# PM.net
KiCad netlist of a schematic drawn in Altium Designer
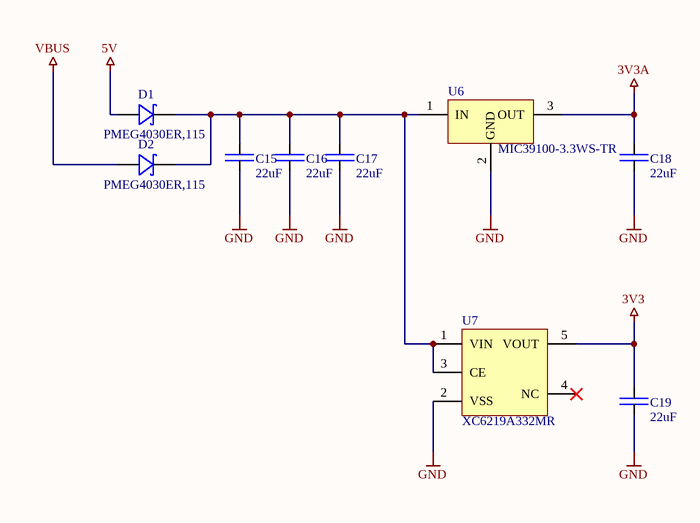
[diagram p0: PM.SchDoc]

(export (version "E")
  (design (tool "Eeschema 10.0.6"))
  (components
    (comp (ref "C15")
      (value "22uF")
      (footprint "SMD Keramikkondensator 0805")
      (description "SMD Ceramic Capacitor E6")
      (libsource (lib "Ceramic Capacitors-E6") (part "E6 - 22uF"))
    )
    (comp (ref "C16")
      (value "22uF")
      (footprint "SMD Keramikkondensator 0805")
      (description "SMD Ceramic Capacitor E6")
      (libsource (lib "Ceramic Capacitors-E6") (part "E6 - 22uF"))
    )
    (comp (ref "C17")
      (value "22uF")
      (footprint "SMD Keramikkondensator 0805")
      (description "SMD Ceramic Capacitor E6")
      (libsource (lib "Ceramic Capacitors-E6") (part "E6 - 22uF"))
    )
    (comp (ref "C18")
      (value "22uF")
      (footprint "SMD Keramikkondensator 0805")
      (description "SMD Ceramic Capacitor E6")
      (libsource (lib "Ceramic Capacitors-E6") (part "E6 - 22uF"))
    )
    (comp (ref "C19")
      (value "22uF")
      (footprint "SMD Keramikkondensator 0805")
      (description "SMD Ceramic Capacitor E6")
      (libsource (lib "Ceramic Capacitors-E6") (part "E6 - 22uF"))
    )
    (comp (ref "D1")
      (value "PMEG4030ER,115")
      (footprint "SMD Diode SOD-123")
      (description "Diode Schottky 3A Surface Mount CFP3")
      (libsource (lib "Diodes") (part "PMEG4030ER,115"))
    )
    (comp (ref "D2")
      (value "PMEG4030ER,115")
      (footprint "SMD Diode SOD-123")
      (description "Diode Schottky 3A Surface Mount CFP3")
      (libsource (lib "Diodes") (part "PMEG4030ER,115"))
    )
    (comp (ref "U6")
      (value "MIC39100-3.3WS-TR")
      (footprint "SMD IC SOT-223-3")
      (description "Linear Voltage Regulator IC Positive Fixed 1 Output 1A SOT-223-3")
      (libsource (lib "Voltage-Converter") (part "MIC39100-3.3WS-TR"))
    )
    (comp (ref "U7")
      (value "XC6219A332MR")
      (footprint "SMD IC SOT-23-5")
      (description "300mA High Speed LDO Regulators with ON/OFF Switch")
      (libsource (lib "Voltage-Converter") (part "XC6219A332MR"))
    )
  )
  (nets
    (net (code "1") (name "3V3") (class "Default")
      (node (ref "C19") (pin "2") (pinfunction "2_2") (pintype "passive"))
      (node (ref "U7") (pin "5") (pinfunction "VOUT_5") (pintype "passive"))
    )
    (net (code "2") (name "3V3A") (class "Default")
      (node (ref "C18") (pin "2") (pinfunction "2_2") (pintype "passive"))
      (node (ref "U6") (pin "3") (pinfunction "OUT_3") (pintype "passive"))
    )
    (net (code "3") (name "5V") (class "Default")
      (node (ref "D1") (pin "A") (pinfunction "A_A") (pintype "passive"))
    )
    (net (code "4") (name "GND") (class "Default")
      (node (ref "C15") (pin "1") (pinfunction "1_1") (pintype "passive"))
      (node (ref "C16") (pin "1") (pinfunction "1_1") (pintype "passive"))
      (node (ref "C17") (pin "1") (pinfunction "1_1") (pintype "passive"))
      (node (ref "C18") (pin "1") (pinfunction "1_1") (pintype "passive"))
      (node (ref "C19") (pin "1") (pinfunction "1_1") (pintype "passive"))
      (node (ref "U6") (pin "2") (pinfunction "GND_2") (pintype "passive"))
      (node (ref "U7") (pin "2") (pinfunction "VSS_2") (pintype "passive"))
    )
    (net (code "5") (name "Net-(U6-IN)") (class "Default")
      (node (ref "C15") (pin "2") (pinfunction "2_2") (pintype "passive"))
      (node (ref "C16") (pin "2") (pinfunction "2_2") (pintype "passive"))
      (node (ref "C17") (pin "2") (pinfunction "2_2") (pintype "passive"))
      (node (ref "D1") (pin "K") (pinfunction "K_K") (pintype "passive"))
      (node (ref "D2") (pin "K") (pinfunction "K_K") (pintype "passive"))
      (node (ref "U6") (pin "1") (pinfunction "IN_1") (pintype "passive"))
      (node (ref "U7") (pin "1") (pinfunction "VIN_1") (pintype "passive"))
      (node (ref "U7") (pin "3") (pinfunction "CE_3") (pintype "passive"))
    )
    (net (code "6") (name "VBUS") (class "Default")
      (node (ref "D2") (pin "A") (pinfunction "A_A") (pintype "passive"))
    )
    (net (code "7") (name "unconnected-(U7-NC-Pad4)") (class "Default")
      (node (ref "U7") (pin "4") (pinfunction "NC_4") (pintype "passive+no_connect"))
    )
  )
)
